# cross.net
KiCad netlist of a schematic drawn in EAGLE
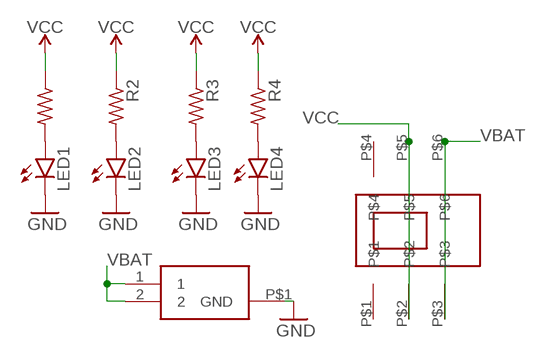
[diagram p0: schematic, sheet 1]

(export (version "E")
  (design (tool "Eeschema 10.0.6"))
  (components
    (comp (ref "LED1")
      (value "LEDCHIP-LED0805")
      (footprint "eagle-import:CHIP-LED0805")
      (libsource (lib "eagle-import") (part "LEDCHIP-LED0805"))
    )
    (comp (ref "LED2")
      (value "LEDCHIP-LED0805")
      (footprint "eagle-import:CHIP-LED0805")
      (libsource (lib "eagle-import") (part "LEDCHIP-LED0805"))
    )
    (comp (ref "LED3")
      (value "LEDCHIP-LED0805")
      (footprint "eagle-import:CHIP-LED0805")
      (libsource (lib "eagle-import") (part "LEDCHIP-LED0805"))
    )
    (comp (ref "LED4")
      (value "LEDCHIP-LED0805")
      (footprint "eagle-import:CHIP-LED0805")
      (libsource (lib "eagle-import") (part "LEDCHIP-LED0805"))
    )
    (comp (ref "R1")
      (value "R-US_R0603")
      (footprint "eagle-import:R0603")
      (libsource (lib "eagle-import") (part "R-US_R0603"))
    )
    (comp (ref "R2")
      (value "R-US_R0603")
      (footprint "eagle-import:R0603")
      (libsource (lib "eagle-import") (part "R-US_R0603"))
    )
    (comp (ref "R3")
      (value "R-US_R0603")
      (footprint "eagle-import:R0603")
      (libsource (lib "eagle-import") (part "R-US_R0603"))
    )
    (comp (ref "R4")
      (value "R-US_R0603")
      (footprint "eagle-import:R0603")
      (libsource (lib "eagle-import") (part "R-US_R0603"))
    )
    (comp (ref "U$1")
      (value "CL-SB-22A-02T-SLIDE-SWITCH-TUCKED-PADS")
      (footprint "eagle-import:CL-SB-22A-02T-DPDT-COMPACT-SWITCH")
      (libsource (lib "eagle-import") (part "CL-SB-22A-02T-SLIDE-SWITCH-TUCKED-PADS"))
    )
    (comp (ref "VBAT")
      (value "BAT-HLD-012-SMT")
      (footprint "eagle-import:BATHLD012SMT")
      (fields (field (name "MOUSER_PART_NUMBER") "712-BAT-HLD-012-SMT"))
      (libsource (lib "eagle-import") (part "BAT-HLD-012-SMT"))
    )
  )
  (nets
    (net (code "1") (name "/VBAT") (class "Default")
      (node (ref "U$1") (pin "P$3") (pinfunction "P$3_P$3") (pintype "bidirectional"))
      (node (ref "U$1") (pin "P$6") (pinfunction "P$6_P$6") (pintype "bidirectional"))
      (node (ref "VBAT") (pin "1") (pinfunction "1_1") (pintype "bidirectional"))
      (node (ref "VBAT") (pin "2") (pinfunction "2_2") (pintype "bidirectional"))
    )
    (net (code "2") (name "GND") (class "Default")
      (node (ref "LED1") (pin "C") (pinfunction "C_C") (pintype "passive"))
      (node (ref "LED2") (pin "C") (pinfunction "C_C") (pintype "passive"))
      (node (ref "LED3") (pin "C") (pinfunction "C_C") (pintype "passive"))
      (node (ref "LED4") (pin "C") (pinfunction "C_C") (pintype "passive"))
      (node (ref "VBAT") (pin "P$1") (pinfunction "GND_P$1") (pintype "bidirectional"))
    )
    (net (code "3") (name "Net-(LED1-PadA)") (class "Default")
      (node (ref "LED1") (pin "A") (pinfunction "A_A") (pintype "passive"))
      (node (ref "R1") (pin "2") (pinfunction "2_2") (pintype "passive"))
    )
    (net (code "4") (name "Net-(LED2-PadA)") (class "Default")
      (node (ref "LED2") (pin "A") (pinfunction "A_A") (pintype "passive"))
      (node (ref "R2") (pin "2") (pinfunction "2_2") (pintype "passive"))
    )
    (net (code "5") (name "Net-(LED3-PadA)") (class "Default")
      (node (ref "LED3") (pin "A") (pinfunction "A_A") (pintype "passive"))
      (node (ref "R3") (pin "2") (pinfunction "2_2") (pintype "passive"))
    )
    (net (code "6") (name "Net-(LED4-PadA)") (class "Default")
      (node (ref "LED4") (pin "A") (pinfunction "A_A") (pintype "passive"))
      (node (ref "R4") (pin "2") (pinfunction "2_2") (pintype "passive"))
    )
    (net (code "7") (name "VCC") (class "Default")
      (node (ref "R1") (pin "1") (pinfunction "1_1") (pintype "passive"))
      (node (ref "R2") (pin "1") (pinfunction "1_1") (pintype "passive"))
      (node (ref "R3") (pin "1") (pinfunction "1_1") (pintype "passive"))
      (node (ref "R4") (pin "1") (pinfunction "1_1") (pintype "passive"))
      (node (ref "U$1") (pin "P$2") (pinfunction "P$2_P$2") (pintype "bidirectional"))
      (node (ref "U$1") (pin "P$5") (pinfunction "P$5_P$5") (pintype "bidirectional"))
    )
    (net (code "8") (name "unconnected-(U$1-PadP$1)") (class "Default")
      (node (ref "U$1") (pin "P$1") (pinfunction "P$1_P$1") (pintype "bidirectional"))
    )
    (net (code "9") (name "unconnected-(U$1-PadP$4)") (class "Default")
      (node (ref "U$1") (pin "P$4") (pinfunction "P$4_P$4") (pintype "bidirectional"))
    )
  )
)
